# Pullup.net
KiCad netlist of a schematic drawn in Altium Designer
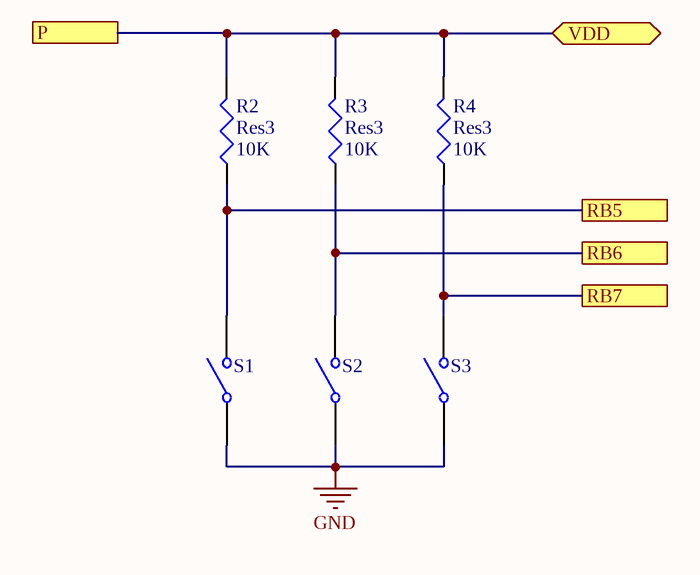
[diagram p0: Pullup.SchDoc]

(export (version "E")
  (design (tool "Eeschema 10.0.6"))
  (components
    (comp (ref "R2")
      (value "Res3")
      (footprint "J1-0603")
      (description "Resistor")
      (fields (field (name "ALTIUM_VALUE") "10K") (field (name "PUBLISHER") "Altium Limited"))
      (libsource (lib "Miscellaneous Devices") (part "Res3"))
    )
    (comp (ref "R3")
      (value "Res3")
      (footprint "J1-0603")
      (description "Resistor")
      (fields (field (name "ALTIUM_VALUE") "10K") (field (name "PUBLISHER") "Altium Limited"))
      (libsource (lib "Miscellaneous Devices") (part "Res3"))
    )
    (comp (ref "R4")
      (value "Res3")
      (footprint "J1-0603")
      (description "Resistor")
      (fields (field (name "ALTIUM_VALUE") "10K") (field (name "PUBLISHER") "Altium Limited"))
      (libsource (lib "Miscellaneous Devices") (part "Res3"))
    )
    (comp (ref "S1")
      (value "SW-SPST")
      (footprint "SPST-2")
      (description "Single-Pole, Single-Throw Switch")
      (fields (field (name "PUBLISHER") "Altium Limited"))
      (libsource (lib "Miscellaneous Devices") (part "SW-SPST"))
    )
    (comp (ref "S2")
      (value "SW-SPST")
      (footprint "SPST-2")
      (description "Single-Pole, Single-Throw Switch")
      (fields (field (name "PUBLISHER") "Altium Limited"))
      (libsource (lib "Miscellaneous Devices") (part "SW-SPST"))
    )
    (comp (ref "S3")
      (value "SW-SPST")
      (footprint "SPST-2")
      (description "Single-Pole, Single-Throw Switch")
      (fields (field (name "PUBLISHER") "Altium Limited"))
      (libsource (lib "Miscellaneous Devices") (part "SW-SPST"))
    )
  )
  (nets
    (net (code "1") (name "/P") (class "Default")
      (node (ref "R2") (pin "2") (pinfunction "2_2") (pintype "passive"))
      (node (ref "R3") (pin "2") (pinfunction "2_2") (pintype "passive"))
      (node (ref "R4") (pin "2") (pinfunction "2_2") (pintype "passive"))
    )
    (net (code "2") (name "/RB5") (class "Default")
      (node (ref "R2") (pin "1") (pinfunction "1_1") (pintype "passive"))
      (node (ref "S1") (pin "2") (pinfunction "NO_2") (pintype "passive"))
    )
    (net (code "3") (name "/RB6") (class "Default")
      (node (ref "R3") (pin "1") (pinfunction "1_1") (pintype "passive"))
      (node (ref "S2") (pin "2") (pinfunction "NO_2") (pintype "passive"))
    )
    (net (code "4") (name "/RB7") (class "Default")
      (node (ref "R4") (pin "1") (pinfunction "1_1") (pintype "passive"))
      (node (ref "S3") (pin "2") (pinfunction "NO_2") (pintype "passive"))
    )
    (net (code "5") (name "GND") (class "Default")
      (node (ref "S1") (pin "1") (pinfunction "COMMON_1") (pintype "passive"))
      (node (ref "S2") (pin "1") (pinfunction "COMMON_1") (pintype "passive"))
      (node (ref "S3") (pin "1") (pinfunction "COMMON_1") (pintype "passive"))
    )
  )
)
